# Sheet2.net
KiCad netlist of a schematic drawn in Altium Designer
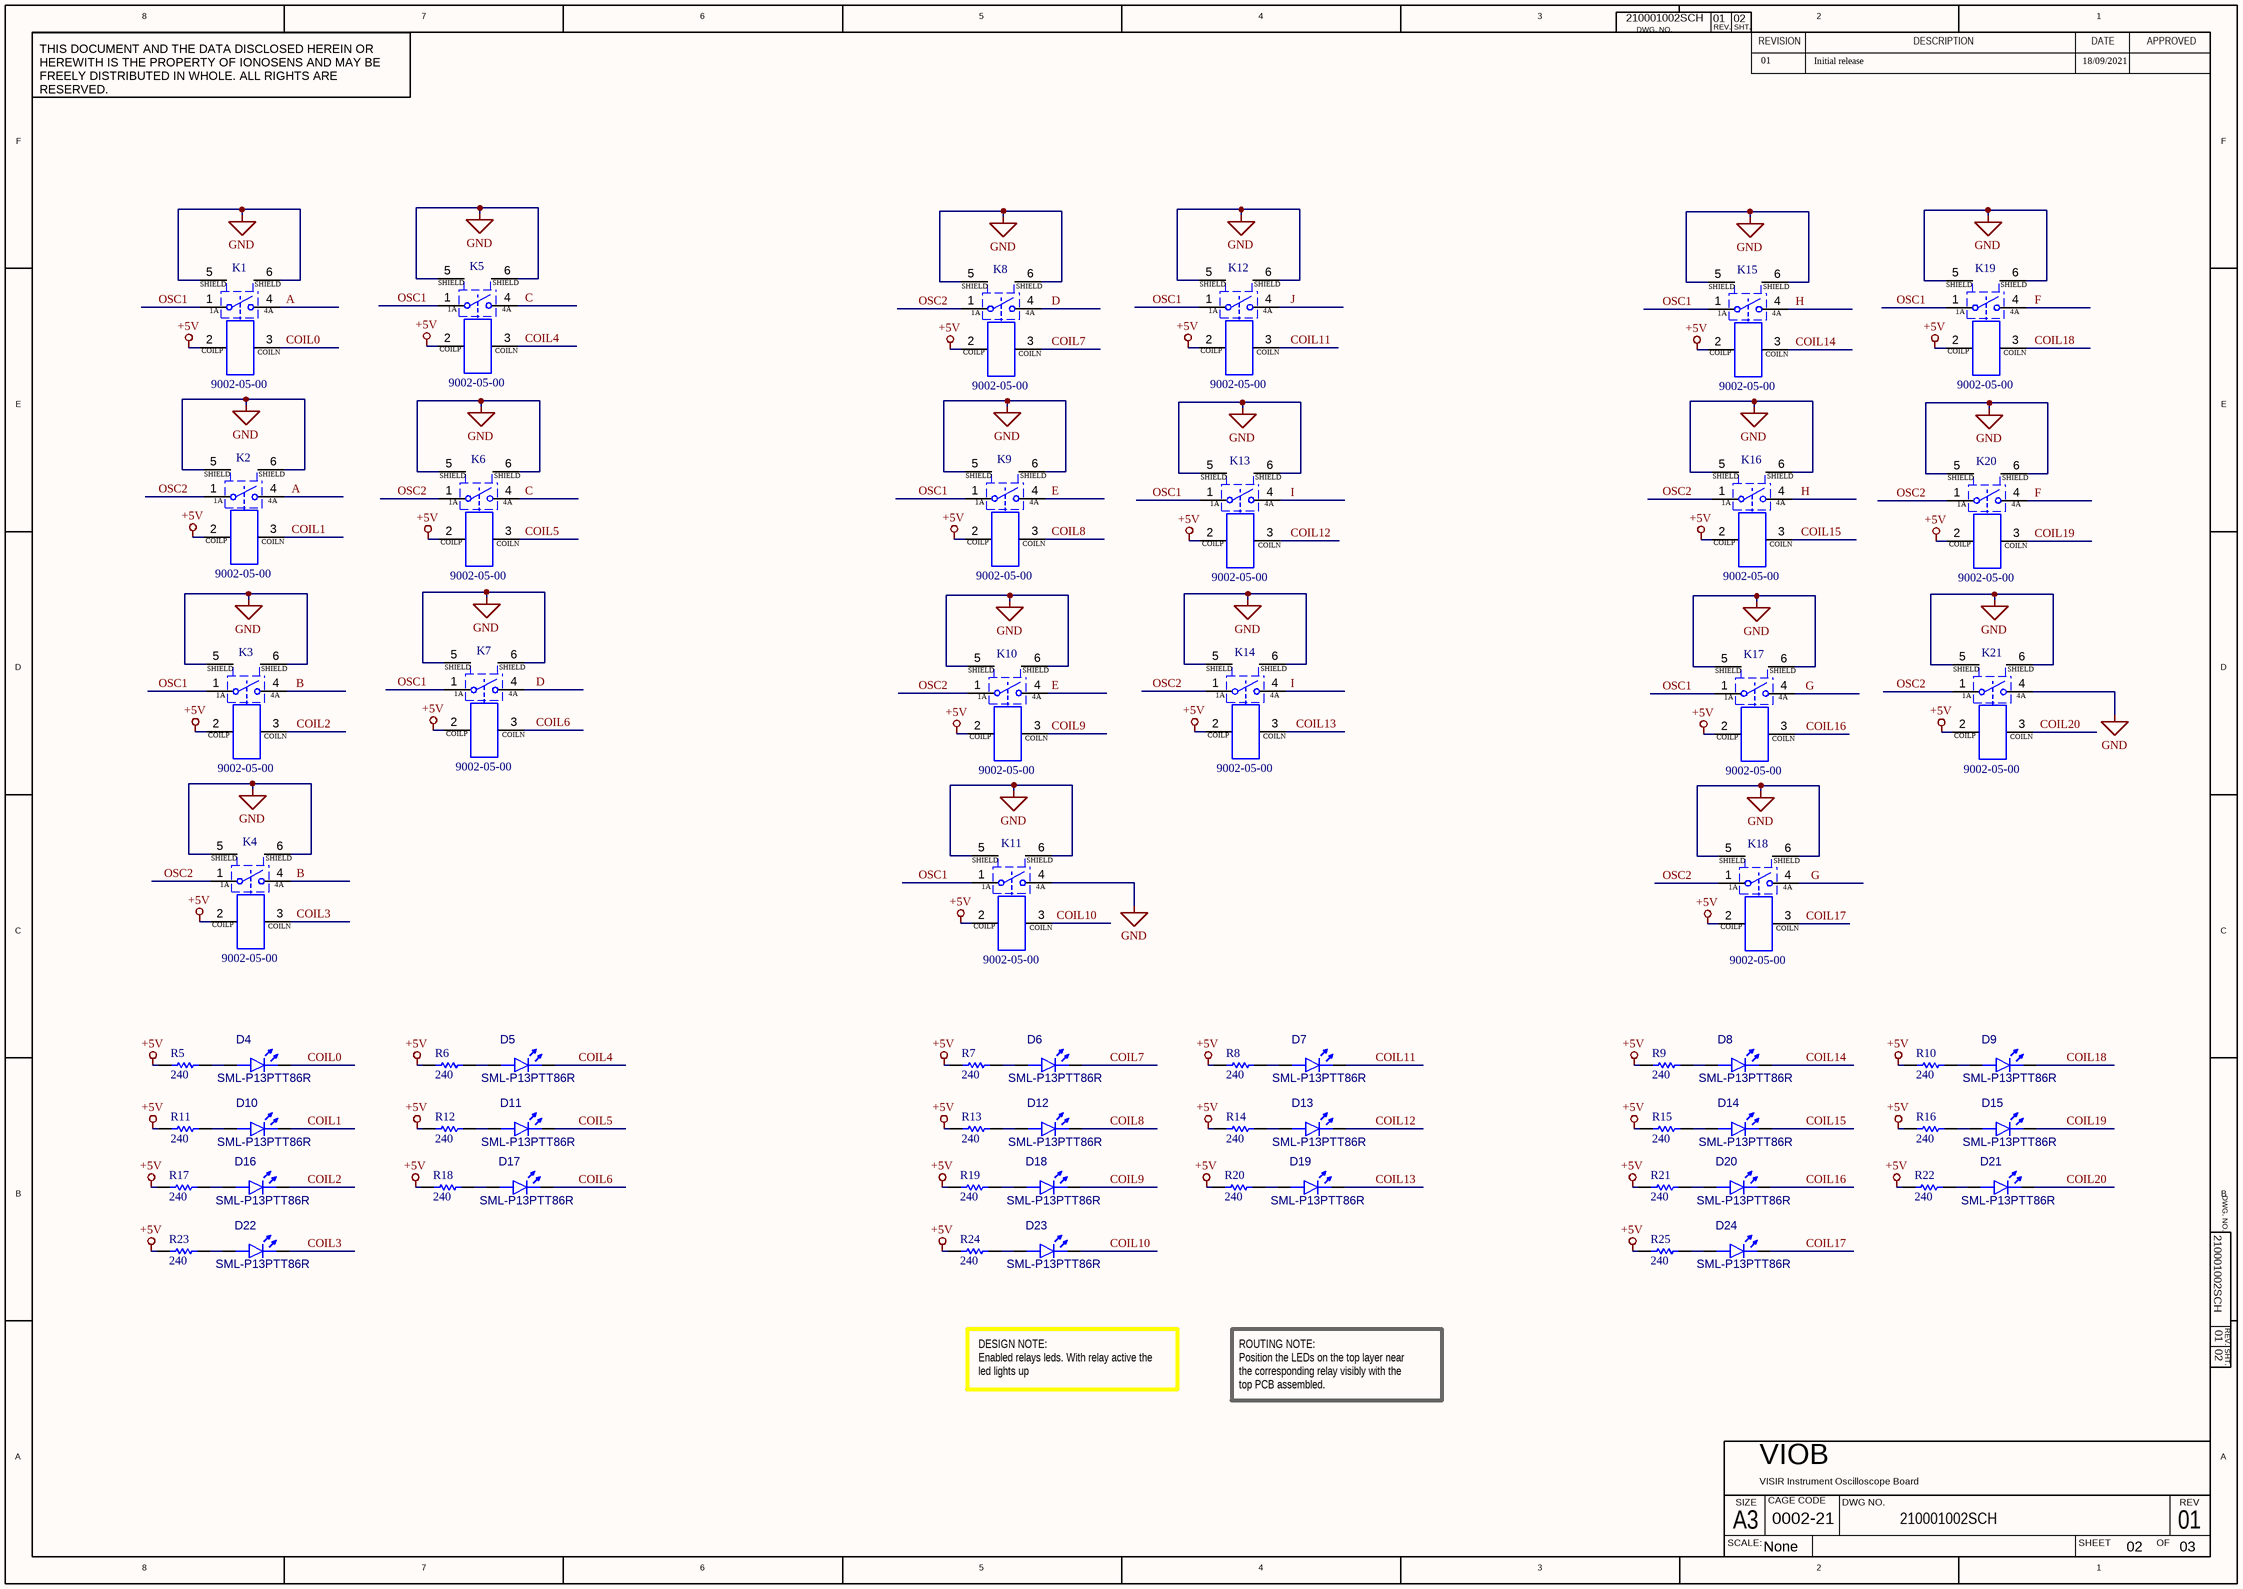
[diagram p0: Sheet2.SchDoc]

(export (version "E")
  (design (tool "Eeschema 10.0.6"))
  (components
    (comp (ref "D4")
      (value "SML-P13PTT86R")
      (footprint "DIOC1005X02R")
      (description "Led green 0402")
      (fields (field (name "MANUFACTURER") "ROHM"))
      (libsource (lib "<Company> Server") (part "LED"))
    )
    (comp (ref "D5")
      (value "SML-P13PTT86R")
      (footprint "DIOC1005X02R")
      (description "Led green 0402")
      (fields (field (name "MANUFACTURER") "ROHM"))
      (libsource (lib "<Company> Server") (part "LED"))
    )
    (comp (ref "D6")
      (value "SML-P13PTT86R")
      (footprint "DIOC1005X02R")
      (description "Led green 0402")
      (fields (field (name "MANUFACTURER") "ROHM"))
      (libsource (lib "<Company> Server") (part "LED"))
    )
    (comp (ref "D7")
      (value "SML-P13PTT86R")
      (footprint "DIOC1005X02R")
      (description "Led green 0402")
      (fields (field (name "MANUFACTURER") "ROHM"))
      (libsource (lib "<Company> Server") (part "LED"))
    )
    (comp (ref "D8")
      (value "SML-P13PTT86R")
      (footprint "DIOC1005X02R")
      (description "Led green 0402")
      (fields (field (name "MANUFACTURER") "ROHM"))
      (libsource (lib "<Company> Server") (part "LED"))
    )
    (comp (ref "D9")
      (value "SML-P13PTT86R")
      (footprint "DIOC1005X02R")
      (description "Led green 0402")
      (fields (field (name "MANUFACTURER") "ROHM"))
      (libsource (lib "<Company> Server") (part "LED"))
    )
    (comp (ref "D10")
      (value "SML-P13PTT86R")
      (footprint "DIOC1005X02R")
      (description "Led green 0402")
      (fields (field (name "MANUFACTURER") "ROHM"))
      (libsource (lib "<Company> Server") (part "LED"))
    )
    (comp (ref "D11")
      (value "SML-P13PTT86R")
      (footprint "DIOC1005X02R")
      (description "Led green 0402")
      (fields (field (name "MANUFACTURER") "ROHM"))
      (libsource (lib "<Company> Server") (part "LED"))
    )
    (comp (ref "D12")
      (value "SML-P13PTT86R")
      (footprint "DIOC1005X02R")
      (description "Led green 0402")
      (fields (field (name "MANUFACTURER") "ROHM"))
      (libsource (lib "<Company> Server") (part "LED"))
    )
    (comp (ref "D13")
      (value "SML-P13PTT86R")
      (footprint "DIOC1005X02R")
      (description "Led green 0402")
      (fields (field (name "MANUFACTURER") "ROHM"))
      (libsource (lib "<Company> Server") (part "LED"))
    )
    (comp (ref "D14")
      (value "SML-P13PTT86R")
      (footprint "DIOC1005X02R")
      (description "Led green 0402")
      (fields (field (name "MANUFACTURER") "ROHM"))
      (libsource (lib "<Company> Server") (part "LED"))
    )
    (comp (ref "D15")
      (value "SML-P13PTT86R")
      (footprint "DIOC1005X02R")
      (description "Led green 0402")
      (fields (field (name "MANUFACTURER") "ROHM"))
      (libsource (lib "<Company> Server") (part "LED"))
    )
    (comp (ref "D16")
      (value "SML-P13PTT86R")
      (footprint "DIOC1005X02R")
      (description "Led green 0402")
      (fields (field (name "MANUFACTURER") "ROHM"))
      (libsource (lib "<Company> Server") (part "LED"))
    )
    (comp (ref "D17")
      (value "SML-P13PTT86R")
      (footprint "DIOC1005X02R")
      (description "Led green 0402")
      (fields (field (name "MANUFACTURER") "ROHM"))
      (libsource (lib "<Company> Server") (part "LED"))
    )
    (comp (ref "D18")
      (value "SML-P13PTT86R")
      (footprint "DIOC1005X02R")
      (description "Led green 0402")
      (fields (field (name "MANUFACTURER") "ROHM"))
      (libsource (lib "<Company> Server") (part "LED"))
    )
    (comp (ref "D19")
      (value "SML-P13PTT86R")
      (footprint "DIOC1005X02R")
      (description "Led green 0402")
      (fields (field (name "MANUFACTURER") "ROHM"))
      (libsource (lib "<Company> Server") (part "LED"))
    )
    (comp (ref "D20")
      (value "SML-P13PTT86R")
      (footprint "DIOC1005X02R")
      (description "Led green 0402")
      (fields (field (name "MANUFACTURER") "ROHM"))
      (libsource (lib "<Company> Server") (part "LED"))
    )
    (comp (ref "D21")
      (value "SML-P13PTT86R")
      (footprint "DIOC1005X02R")
      (description "Led green 0402")
      (fields (field (name "MANUFACTURER") "ROHM"))
      (libsource (lib "<Company> Server") (part "LED"))
    )
    (comp (ref "D22")
      (value "SML-P13PTT86R")
      (footprint "DIOC1005X02R")
      (description "Led green 0402")
      (fields (field (name "MANUFACTURER") "ROHM"))
      (libsource (lib "<Company> Server") (part "LED"))
    )
    (comp (ref "D23")
      (value "SML-P13PTT86R")
      (footprint "DIOC1005X02R")
      (description "Led green 0402")
      (fields (field (name "MANUFACTURER") "ROHM"))
      (libsource (lib "<Company> Server") (part "LED"))
    )
    (comp (ref "D24")
      (value "SML-P13PTT86R")
      (footprint "DIOC1005X02R")
      (description "Led green 0402")
      (fields (field (name "MANUFACTURER") "ROHM"))
      (libsource (lib "<Company> Server") (part "LED"))
    )
    (comp (ref "K1")
      (value "9002-05-00")
      (footprint "SIP564W40P254L1980H810Q6 - Cloned")
      (description "Reed Relay 5VDC 350Ohm 0.5A SPST-NO THT")
      (fields (field (name "MANUFACTURER") "COTO"))
      (libsource (lib "<Company> Server") (part "9002-XX-XX"))
    )
    (comp (ref "K2")
      (value "9002-05-00")
      (footprint "SIP564W40P254L1980H810Q6 - Cloned")
      (description "Reed Relay 5VDC 350Ohm 0.5A SPST-NO THT")
      (fields (field (name "MANUFACTURER") "COTO"))
      (libsource (lib "<Company> Server") (part "9002-XX-XX"))
    )
    (comp (ref "K3")
      (value "9002-05-00")
      (footprint "SIP564W40P254L1980H810Q6 - Cloned")
      (description "Reed Relay 5VDC 350Ohm 0.5A SPST-NO THT")
      (fields (field (name "MANUFACTURER") "COTO"))
      (libsource (lib "<Company> Server") (part "9002-XX-XX"))
    )
    (comp (ref "K4")
      (value "9002-05-00")
      (footprint "SIP564W40P254L1980H810Q6 - Cloned")
      (description "Reed Relay 5VDC 350Ohm 0.5A SPST-NO THT")
      (fields (field (name "MANUFACTURER") "COTO"))
      (libsource (lib "<Company> Server") (part "9002-XX-XX"))
    )
    (comp (ref "K5")
      (value "9002-05-00")
      (footprint "SIP564W40P254L1980H810Q6 - Cloned")
      (description "Reed Relay 5VDC 350Ohm 0.5A SPST-NO THT")
      (fields (field (name "MANUFACTURER") "COTO"))
      (libsource (lib "<Company> Server") (part "9002-XX-XX"))
    )
    (comp (ref "K6")
      (value "9002-05-00")
      (footprint "SIP564W40P254L1980H810Q6 - Cloned")
      (description "Reed Relay 5VDC 350Ohm 0.5A SPST-NO THT")
      (fields (field (name "MANUFACTURER") "COTO"))
      (libsource (lib "<Company> Server") (part "9002-XX-XX"))
    )
    (comp (ref "K7")
      (value "9002-05-00")
      (footprint "SIP564W40P254L1980H810Q6 - Cloned")
      (description "Reed Relay 5VDC 350Ohm 0.5A SPST-NO THT")
      (fields (field (name "MANUFACTURER") "COTO"))
      (libsource (lib "<Company> Server") (part "9002-XX-XX"))
    )
    (comp (ref "K8")
      (value "9002-05-00")
      (footprint "SIP564W40P254L1980H810Q6 - Cloned")
      (description "Reed Relay 5VDC 350Ohm 0.5A SPST-NO THT")
      (fields (field (name "MANUFACTURER") "COTO"))
      (libsource (lib "<Company> Server") (part "9002-XX-XX"))
    )
    (comp (ref "K9")
      (value "9002-05-00")
      (footprint "SIP564W40P254L1980H810Q6 - Cloned")
      (description "Reed Relay 5VDC 350Ohm 0.5A SPST-NO THT")
      (fields (field (name "MANUFACTURER") "COTO"))
      (libsource (lib "<Company> Server") (part "9002-XX-XX"))
    )
    (comp (ref "K10")
      (value "9002-05-00")
      (footprint "SIP564W40P254L1980H810Q6 - Cloned")
      (description "Reed Relay 5VDC 350Ohm 0.5A SPST-NO THT")
      (fields (field (name "MANUFACTURER") "COTO"))
      (libsource (lib "<Company> Server") (part "9002-XX-XX"))
    )
    (comp (ref "K11")
      (value "9002-05-00")
      (footprint "SIP564W40P254L1980H810Q6 - Cloned")
      (description "Reed Relay 5VDC 350Ohm 0.5A SPST-NO THT")
      (fields (field (name "MANUFACTURER") "COTO"))
      (libsource (lib "<Company> Server") (part "9002-XX-XX"))
    )
    (comp (ref "K12")
      (value "9002-05-00")
      (footprint "SIP564W40P254L1980H810Q6 - Cloned")
      (description "Reed Relay 5VDC 350Ohm 0.5A SPST-NO THT")
      (fields (field (name "MANUFACTURER") "COTO"))
      (libsource (lib "<Company> Server") (part "9002-XX-XX"))
    )
    (comp (ref "K13")
      (value "9002-05-00")
      (footprint "SIP564W40P254L1980H810Q6 - Cloned")
      (description "Reed Relay 5VDC 350Ohm 0.5A SPST-NO THT")
      (fields (field (name "MANUFACTURER") "COTO"))
      (libsource (lib "<Company> Server") (part "9002-XX-XX"))
    )
    (comp (ref "K14")
      (value "9002-05-00")
      (footprint "SIP564W40P254L1980H810Q6 - Cloned")
      (description "Reed Relay 5VDC 350Ohm 0.5A SPST-NO THT")
      (fields (field (name "MANUFACTURER") "COTO"))
      (libsource (lib "<Company> Server") (part "9002-XX-XX"))
    )
    (comp (ref "K15")
      (value "9002-05-00")
      (footprint "SIP564W40P254L1980H810Q6 - Cloned")
      (description "Reed Relay 5VDC 350Ohm 0.5A SPST-NO THT")
      (fields (field (name "MANUFACTURER") "COTO"))
      (libsource (lib "<Company> Server") (part "9002-XX-XX"))
    )
    (comp (ref "K16")
      (value "9002-05-00")
      (footprint "SIP564W40P254L1980H810Q6 - Cloned")
      (description "Reed Relay 5VDC 350Ohm 0.5A SPST-NO THT")
      (fields (field (name "MANUFACTURER") "COTO"))
      (libsource (lib "<Company> Server") (part "9002-XX-XX"))
    )
    (comp (ref "K17")
      (value "9002-05-00")
      (footprint "SIP564W40P254L1980H810Q6 - Cloned")
      (description "Reed Relay 5VDC 350Ohm 0.5A SPST-NO THT")
      (fields (field (name "MANUFACTURER") "COTO"))
      (libsource (lib "<Company> Server") (part "9002-XX-XX"))
    )
    (comp (ref "K18")
      (value "9002-05-00")
      (footprint "SIP564W40P254L1980H810Q6 - Cloned")
      (description "Reed Relay 5VDC 350Ohm 0.5A SPST-NO THT")
      (fields (field (name "MANUFACTURER") "COTO"))
      (libsource (lib "<Company> Server") (part "9002-XX-XX"))
    )
    (comp (ref "K19")
      (value "9002-05-00")
      (footprint "SIP564W40P254L1980H810Q6 - Cloned")
      (description "Reed Relay 5VDC 350Ohm 0.5A SPST-NO THT")
      (fields (field (name "MANUFACTURER") "COTO"))
      (libsource (lib "<Company> Server") (part "9002-XX-XX"))
    )
    (comp (ref "K20")
      (value "9002-05-00")
      (footprint "SIP564W40P254L1980H810Q6 - Cloned")
      (description "Reed Relay 5VDC 350Ohm 0.5A SPST-NO THT")
      (fields (field (name "MANUFACTURER") "COTO"))
      (libsource (lib "<Company> Server") (part "9002-XX-XX"))
    )
    (comp (ref "K21")
      (value "9002-05-00")
      (footprint "SIP564W40P254L1980H810Q6 - Cloned")
      (description "Reed Relay 5VDC 350Ohm 0.5A SPST-NO THT")
      (fields (field (name "MANUFACTURER") "COTO"))
      (libsource (lib "<Company> Server") (part "9002-XX-XX"))
    )
    (comp (ref "R5")
      (value "240")
      (footprint "RESC1005X04M")
      (description "RES SMD 240 OHM 1% 1/16W 0402")
      (fields (field (name "MANUFACTURER") "Yageo") (field (name "TOLERANCE") "1%"))
      (libsource (lib "<Company> Server") (part "Resistor"))
    )
    (comp (ref "R6")
      (value "240")
      (footprint "RESC1005X04M")
      (description "RES SMD 240 OHM 1% 1/16W 0402")
      (fields (field (name "MANUFACTURER") "Yageo") (field (name "TOLERANCE") "1%"))
      (libsource (lib "<Company> Server") (part "Resistor"))
    )
    (comp (ref "R7")
      (value "240")
      (footprint "RESC1005X04M")
      (description "RES SMD 240 OHM 1% 1/16W 0402")
      (fields (field (name "MANUFACTURER") "Yageo") (field (name "TOLERANCE") "1%"))
      (libsource (lib "<Company> Server") (part "Resistor"))
    )
    (comp (ref "R8")
      (value "240")
      (footprint "RESC1005X04M")
      (description "RES SMD 240 OHM 1% 1/16W 0402")
      (fields (field (name "MANUFACTURER") "Yageo") (field (name "TOLERANCE") "1%"))
      (libsource (lib "<Company> Server") (part "Resistor"))
    )
    (comp (ref "R9")
      (value "240")
      (footprint "RESC1005X04M")
      (description "RES SMD 240 OHM 1% 1/16W 0402")
      (fields (field (name "MANUFACTURER") "Yageo") (field (name "TOLERANCE") "1%"))
      (libsource (lib "<Company> Server") (part "Resistor"))
    )
    (comp (ref "R10")
      (value "240")
      (footprint "RESC1005X04M")
      (description "RES SMD 240 OHM 1% 1/16W 0402")
      (fields (field (name "MANUFACTURER") "Yageo") (field (name "TOLERANCE") "1%"))
      (libsource (lib "<Company> Server") (part "Resistor"))
    )
    (comp (ref "R11")
      (value "240")
      (footprint "RESC1005X04M")
      (description "RES SMD 240 OHM 1% 1/16W 0402")
      (fields (field (name "MANUFACTURER") "Yageo") (field (name "TOLERANCE") "1%"))
      (libsource (lib "<Company> Server") (part "Resistor"))
    )
    (comp (ref "R12")
      (value "240")
      (footprint "RESC1005X04M")
      (description "RES SMD 240 OHM 1% 1/16W 0402")
      (fields (field (name "MANUFACTURER") "Yageo") (field (name "TOLERANCE") "1%"))
      (libsource (lib "<Company> Server") (part "Resistor"))
    )
    (comp (ref "R13")
      (value "240")
      (footprint "RESC1005X04M")
      (description "RES SMD 240 OHM 1% 1/16W 0402")
      (fields (field (name "MANUFACTURER") "Yageo") (field (name "TOLERANCE") "1%"))
      (libsource (lib "<Company> Server") (part "Resistor"))
    )
    (comp (ref "R14")
      (value "240")
      (footprint "RESC1005X04M")
      (description "RES SMD 240 OHM 1% 1/16W 0402")
      (fields (field (name "MANUFACTURER") "Yageo") (field (name "TOLERANCE") "1%"))
      (libsource (lib "<Company> Server") (part "Resistor"))
    )
    (comp (ref "R15")
      (value "240")
      (footprint "RESC1005X04M")
      (description "RES SMD 240 OHM 1% 1/16W 0402")
      (fields (field (name "MANUFACTURER") "Yageo") (field (name "TOLERANCE") "1%"))
      (libsource (lib "<Company> Server") (part "Resistor"))
    )
    (comp (ref "R16")
      (value "240")
      (footprint "RESC1005X04M")
      (description "RES SMD 240 OHM 1% 1/16W 0402")
      (fields (field (name "MANUFACTURER") "Yageo") (field (name "TOLERANCE") "1%"))
      (libsource (lib "<Company> Server") (part "Resistor"))
    )
    (comp (ref "R17")
      (value "240")
      (footprint "RESC1005X04M")
      (description "RES SMD 240 OHM 1% 1/16W 0402")
      (fields (field (name "MANUFACTURER") "Yageo") (field (name "TOLERANCE") "1%"))
      (libsource (lib "<Company> Server") (part "Resistor"))
    )
    (comp (ref "R18")
      (value "240")
      (footprint "RESC1005X04M")
      (description "RES SMD 240 OHM 1% 1/16W 0402")
      (fields (field (name "MANUFACTURER") "Yageo") (field (name "TOLERANCE") "1%"))
      (libsource (lib "<Company> Server") (part "Resistor"))
    )
    (comp (ref "R19")
      (value "240")
      (footprint "RESC1005X04M")
      (description "RES SMD 240 OHM 1% 1/16W 0402")
      (fields (field (name "MANUFACTURER") "Yageo") (field (name "TOLERANCE") "1%"))
      (libsource (lib "<Company> Server") (part "Resistor"))
    )
    (comp (ref "R20")
      (value "240")
      (footprint "RESC1005X04M")
      (description "RES SMD 240 OHM 1% 1/16W 0402")
      (fields (field (name "MANUFACTURER") "Yageo") (field (name "TOLERANCE") "1%"))
      (libsource (lib "<Company> Server") (part "Resistor"))
    )
    (comp (ref "R21")
      (value "240")
      (footprint "RESC1005X04M")
      (description "RES SMD 240 OHM 1% 1/16W 0402")
      (fields (field (name "MANUFACTURER") "Yageo") (field (name "TOLERANCE") "1%"))
      (libsource (lib "<Company> Server") (part "Resistor"))
    )
    (comp (ref "R22")
      (value "240")
      (footprint "RESC1005X04M")
      (description "RES SMD 240 OHM 1% 1/16W 0402")
      (fields (field (name "MANUFACTURER") "Yageo") (field (name "TOLERANCE") "1%"))
      (libsource (lib "<Company> Server") (part "Resistor"))
    )
    (comp (ref "R23")
      (value "240")
      (footprint "RESC1005X04M")
      (description "RES SMD 240 OHM 1% 1/16W 0402")
      (fields (field (name "MANUFACTURER") "Yageo") (field (name "TOLERANCE") "1%"))
      (libsource (lib "<Company> Server") (part "Resistor"))
    )
    (comp (ref "R24")
      (value "240")
      (footprint "RESC1005X04M")
      (description "RES SMD 240 OHM 1% 1/16W 0402")
      (fields (field (name "MANUFACTURER") "Yageo") (field (name "TOLERANCE") "1%"))
      (libsource (lib "<Company> Server") (part "Resistor"))
    )
    (comp (ref "R25")
      (value "240")
      (footprint "RESC1005X04M")
      (description "RES SMD 240 OHM 1% 1/16W 0402")
      (fields (field (name "MANUFACTURER") "Yageo") (field (name "TOLERANCE") "1%"))
      (libsource (lib "<Company> Server") (part "Resistor"))
    )
  )
  (nets
    (net (code "1") (name "+5V") (class "Default")
      (node (ref "K1") (pin "2") (pinfunction "COILP_2") (pintype "passive"))
      (node (ref "K10") (pin "2") (pinfunction "COILP_2") (pintype "passive"))
      (node (ref "K11") (pin "2") (pinfunction "COILP_2") (pintype "passive"))
      (node (ref "K12") (pin "2") (pinfunction "COILP_2") (pintype "passive"))
      (node (ref "K13") (pin "2") (pinfunction "COILP_2") (pintype "passive"))
      (node (ref "K14") (pin "2") (pinfunction "COILP_2") (pintype "passive"))
      (node (ref "K15") (pin "2") (pinfunction "COILP_2") (pintype "passive"))
      (node (ref "K16") (pin "2") (pinfunction "COILP_2") (pintype "passive"))
      (node (ref "K17") (pin "2") (pinfunction "COILP_2") (pintype "passive"))
      (node (ref "K18") (pin "2") (pinfunction "COILP_2") (pintype "passive"))
      (node (ref "K19") (pin "2") (pinfunction "COILP_2") (pintype "passive"))
      (node (ref "K2") (pin "2") (pinfunction "COILP_2") (pintype "passive"))
      (node (ref "K20") (pin "2") (pinfunction "COILP_2") (pintype "passive"))
      (node (ref "K21") (pin "2") (pinfunction "COILP_2") (pintype "passive"))
      (node (ref "K3") (pin "2") (pinfunction "COILP_2") (pintype "passive"))
      (node (ref "K4") (pin "2") (pinfunction "COILP_2") (pintype "passive"))
      (node (ref "K5") (pin "2") (pinfunction "COILP_2") (pintype "passive"))
      (node (ref "K6") (pin "2") (pinfunction "COILP_2") (pintype "passive"))
      (node (ref "K7") (pin "2") (pinfunction "COILP_2") (pintype "passive"))
      (node (ref "K8") (pin "2") (pinfunction "COILP_2") (pintype "passive"))
      (node (ref "K9") (pin "2") (pinfunction "COILP_2") (pintype "passive"))
      (node (ref "R10") (pin "1") (pinfunction "1_1") (pintype "passive"))
      (node (ref "R11") (pin "1") (pinfunction "1_1") (pintype "passive"))
      (node (ref "R12") (pin "1") (pinfunction "1_1") (pintype "passive"))
      (node (ref "R13") (pin "1") (pinfunction "1_1") (pintype "passive"))
      (node (ref "R14") (pin "1") (pinfunction "1_1") (pintype "passive"))
      (node (ref "R15") (pin "1") (pinfunction "1_1") (pintype "passive"))
      (node (ref "R16") (pin "1") (pinfunction "1_1") (pintype "passive"))
      (node (ref "R17") (pin "1") (pinfunction "1_1") (pintype "passive"))
      (node (ref "R18") (pin "1") (pinfunction "1_1") (pintype "passive"))
      (node (ref "R19") (pin "1") (pinfunction "1_1") (pintype "passive"))
      (node (ref "R20") (pin "1") (pinfunction "1_1") (pintype "passive"))
      (node (ref "R21") (pin "1") (pinfunction "1_1") (pintype "passive"))
      (node (ref "R22") (pin "1") (pinfunction "1_1") (pintype "passive"))
      (node (ref "R23") (pin "1") (pinfunction "1_1") (pintype "passive"))
      (node (ref "R24") (pin "1") (pinfunction "1_1") (pintype "passive"))
      (node (ref "R25") (pin "1") (pinfunction "1_1") (pintype "passive"))
      (node (ref "R5") (pin "1") (pinfunction "1_1") (pintype "passive"))
      (node (ref "R6") (pin "1") (pinfunction "1_1") (pintype "passive"))
      (node (ref "R7") (pin "1") (pinfunction "1_1") (pintype "passive"))
      (node (ref "R8") (pin "1") (pinfunction "1_1") (pintype "passive"))
      (node (ref "R9") (pin "1") (pinfunction "1_1") (pintype "passive"))
    )
    (net (code "2") (name "/A") (class "Default")
      (node (ref "K1") (pin "4") (pinfunction "4A_4") (pintype "passive"))
      (node (ref "K2") (pin "4") (pinfunction "4A_4") (pintype "passive"))
    )
    (net (code "3") (name "/B") (class "Default")
      (node (ref "K3") (pin "4") (pinfunction "4A_4") (pintype "passive"))
      (node (ref "K4") (pin "4") (pinfunction "4A_4") (pintype "passive"))
    )
    (net (code "4") (name "/C") (class "Default")
      (node (ref "K5") (pin "4") (pinfunction "4A_4") (pintype "passive"))
      (node (ref "K6") (pin "4") (pinfunction "4A_4") (pintype "passive"))
    )
    (net (code "5") (name "/COIL0") (class "Default")
      (node (ref "D4") (pin "1") (pinfunction "K_1") (pintype "passive"))
      (node (ref "K1") (pin "3") (pinfunction "COILN_3") (pintype "passive"))
    )
    (net (code "6") (name "/COIL1") (class "Default")
      (node (ref "D10") (pin "1") (pinfunction "K_1") (pintype "passive"))
      (node (ref "K2") (pin "3") (pinfunction "COILN_3") (pintype "passive"))
    )
    (net (code "7") (name "/COIL2") (class "Default")
      (node (ref "D16") (pin "1") (pinfunction "K_1") (pintype "passive"))
      (node (ref "K3") (pin "3") (pinfunction "COILN_3") (pintype "passive"))
    )
    (net (code "8") (name "/COIL3") (class "Default")
      (node (ref "D22") (pin "1") (pinfunction "K_1") (pintype "passive"))
      (node (ref "K4") (pin "3") (pinfunction "COILN_3") (pintype "passive"))
    )
    (net (code "9") (name "/COIL4") (class "Default")
      (node (ref "D5") (pin "1") (pinfunction "K_1") (pintype "passive"))
      (node (ref "K5") (pin "3") (pinfunction "COILN_3") (pintype "passive"))
    )
    (net (code "10") (name "/COIL5") (class "Default")
      (node (ref "D11") (pin "1") (pinfunction "K_1") (pintype "passive"))
      (node (ref "K6") (pin "3") (pinfunction "COILN_3") (pintype "passive"))
    )
    (net (code "11") (name "/COIL6") (class "Default")
      (node (ref "D17") (pin "1") (pinfunction "K_1") (pintype "passive"))
      (node (ref "K7") (pin "3") (pinfunction "COILN_3") (pintype "passive"))
    )
    (net (code "12") (name "/COIL7") (class "Default")
      (node (ref "D6") (pin "1") (pinfunction "K_1") (pintype "passive"))
      (node (ref "K8") (pin "3") (pinfunction "COILN_3") (pintype "passive"))
    )
    (net (code "13") (name "/COIL8") (class "Default")
      (node (ref "D12") (pin "1") (pinfunction "K_1") (pintype "passive"))
      (node (ref "K9") (pin "3") (pinfunction "COILN_3") (pintype "passive"))
    )
    (net (code "14") (name "/COIL9") (class "Default")
      (node (ref "D18") (pin "1") (pinfunction "K_1") (pintype "passive"))
      (node (ref "K10") (pin "3") (pinfunction "COILN_3") (pintype "passive"))
    )
    (net (code "15") (name "/COIL10") (class "Default")
      (node (ref "D23") (pin "1") (pinfunction "K_1") (pintype "passive"))
      (node (ref "K11") (pin "3") (pinfunction "COILN_3") (pintype "passive"))
    )
    (net (code "16") (name "/COIL11") (class "Default")
      (node (ref "D7") (pin "1") (pinfunction "K_1") (pintype "passive"))
      (node (ref "K12") (pin "3") (pinfunction "COILN_3") (pintype "passive"))
    )
    (net (code "17") (name "/COIL12") (class "Default")
      (node (ref "D13") (pin "1") (pinfunction "K_1") (pintype "passive"))
      (node (ref "K13") (pin "3") (pinfunction "COILN_3") (pintype "passive"))
    )
    (net (code "18") (name "/COIL13") (class "Default")
      (node (ref "D19") (pin "1") (pinfunction "K_1") (pintype "passive"))
      (node (ref "K14") (pin "3") (pinfunction "COILN_3") (pintype "passive"))
    )
    (net (code "19") (name "/COIL14") (class "Default")
      (node (ref "D8") (pin "1") (pinfunction "K_1") (pintype "passive"))
      (node (ref "K15") (pin "3") (pinfunction "COILN_3") (pintype "passive"))
    )
    (net (code "20") (name "/COIL15") (class "Default")
      (node (ref "D14") (pin "1") (pinfunction "K_1") (pintype "passive"))
      (node (ref "K16") (pin "3") (pinfunction "COILN_3") (pintype "passive"))
    )
    (net (code "21") (name "/COIL16") (class "Default")
      (node (ref "D20") (pin "1") (pinfunction "K_1") (pintype "passive"))
      (node (ref "K17") (pin "3") (pinfunction "COILN_3") (pintype "passive"))
    )
    (net (code "22") (name "/COIL17") (class "Default")
      (node (ref "D24") (pin "1") (pinfunction "K_1") (pintype "passive"))
      (node (ref "K18") (pin "3") (pinfunction "COILN_3") (pintype "passive"))
    )
    (net (code "23") (name "/COIL18") (class "Default")
      (node (ref "D9") (pin "1") (pinfunction "K_1") (pintype "passive"))
      (node (ref "K19") (pin "3") (pinfunction "COILN_3") (pintype "passive"))
    )
    (net (code "24") (name "/COIL19") (class "Default")
      (node (ref "D15") (pin "1") (pinfunction "K_1") (pintype "passive"))
      (node (ref "K20") (pin "3") (pinfunction "COILN_3") (pintype "passive"))
    )
    (net (code "25") (name "/COIL20") (class "Default")
      (node (ref "D21") (pin "1") (pinfunction "K_1") (pintype "passive"))
      (node (ref "K21") (pin "3") (pinfunction "COILN_3") (pintype "passive"))
    )
    (net (code "26") (name "/D") (class "Default")
      (node (ref "K7") (pin "4") (pinfunction "4A_4") (pintype "passive"))
      (node (ref "K8") (pin "4") (pinfunction "4A_4") (pintype "passive"))
    )
    (net (code "27") (name "/E") (class "Default")
      (node (ref "K10") (pin "4") (pinfunction "4A_4") (pintype "passive"))
      (node (ref "K9") (pin "4") (pinfunction "4A_4") (pintype "passive"))
    )
    (net (code "28") (name "/F") (class "Default")
      (node (ref "K19") (pin "4") (pinfunction "4A_4") (pintype "passive"))
      (node (ref "K20") (pin "4") (pinfunction "4A_4") (pintype "passive"))
    )
    (net (code "29") (name "/G") (class "Default")
      (node (ref "K17") (pin "4") (pinfunction "4A_4") (pintype "passive"))
      (node (ref "K18") (pin "4") (pinfunction "4A_4") (pintype "passive"))
    )
    (net (code "30") (name "/H") (class "Default")
      (node (ref "K15") (pin "4") (pinfunction "4A_4") (pintype "passive"))
      (node (ref "K16") (pin "4") (pinfunction "4A_4") (pintype "passive"))
    )
    (net (code "31") (name "/I") (class "Default")
      (node (ref "K13") (pin "4") (pinfunction "4A_4") (pintype "passive"))
      (node (ref "K14") (pin "4") (pinfunction "4A_4") (pintype "passive"))
    )
    (net (code "32") (name "/J") (class "Default")
      (node (ref "K12") (pin "4") (pinfunction "4A_4") (pintype "passive"))
    )
    (net (code "33") (name "/OSC1") (class "Default")
      (node (ref "K1") (pin "1") (pinfunction "1A_1") (pintype "passive"))
      (node (ref "K11") (pin "1") (pinfunction "1A_1") (pintype "passive"))
      (node (ref "K12") (pin "1") (pinfunction "1A_1") (pintype "passive"))
      (node (ref "K13") (pin "1") (pinfunction "1A_1") (pintype "passive"))
      (node (ref "K15") (pin "1") (pinfunction "1A_1") (pintype "passive"))
      (node (ref "K17") (pin "1") (pinfunction "1A_1") (pintype "passive"))
      (node (ref "K19") (pin "1") (pinfunction "1A_1") (pintype "passive"))
      (node (ref "K3") (pin "1") (pinfunction "1A_1") (pintype "passive"))
      (node (ref "K5") (pin "1") (pinfunction "1A_1") (pintype "passive"))
      (node (ref "K7") (pin "1") (pinfunction "1A_1") (pintype "passive"))
      (node (ref "K9") (pin "1") (pinfunction "1A_1") (pintype "passive"))
    )
    (net (code "34") (name "/OSC2") (class "Default")
      (node (ref "K10") (pin "1") (pinfunction "1A_1") (pintype "passive"))
      (node (ref "K14") (pin "1") (pinfunction "1A_1") (pintype "passive"))
      (node (ref "K16") (pin "1") (pinfunction "1A_1") (pintype "passive"))
      (node (ref "K18") (pin "1") (pinfunction "1A_1") (pintype "passive"))
      (node (ref "K2") (pin "1") (pinfunction "1A_1") (pintype "passive"))
      (node (ref "K20") (pin "1") (pinfunction "1A_1") (pintype "passive"))
      (node (ref "K21") (pin "1") (pinfunction "1A_1") (pintype "passive"))
      (node (ref "K4") (pin "1") (pinfunction "1A_1") (pintype "passive"))
      (node (ref "K6") (pin "1") (pinfunction "1A_1") (pintype "passive"))
      (node (ref "K8") (pin "1") (pinfunction "1A_1") (pintype "passive"))
    )
    (net (code "35") (name "GND") (class "Default")
      (node (ref "K1") (pin "5") (pinfunction "Shield_5") (pintype "passive"))
      (node (ref "K1") (pin "6") (pinfunction "Shield_6") (pintype "passive"))
      (node (ref "K10") (pin "5") (pinfunction "Shield_5") (pintype "passive"))
      (node (ref "K10") (pin "6") (pinfunction "Shield_6") (pintype "passive"))
      (node (ref "K11") (pin "4") (pinfunction "4A_4") (pintype "passive"))
      (node (ref "K11") (pin "5") (pinfunction "Shield_5") (pintype "passive"))
      (node (ref "K11") (pin "6") (pinfunction "Shield_6") (pintype "passive"))
      (node (ref "K12") (pin "5") (pinfunction "Shield_5") (pintype "passive"))
      (node (ref "K12") (pin "6") (pinfunction "Shield_6") (pintype "passive"))
      (node (ref "K13") (pin "5") (pinfunction "Shield_5") (pintype "passive"))
      (node (ref "K13") (pin "6") (pinfunction "Shield_6") (pintype "passive"))
      (node (ref "K14") (pin "5") (pinfunction "Shield_5") (pintype "passive"))
      (node (ref "K14") (pin "6") (pinfunction "Shield_6") (pintype "passive"))
      (node (ref "K15") (pin "5") (pinfunction "Shield_5") (pintype "passive"))
      (node (ref "K15") (pin "6") (pinfunction "Shield_6") (pintype "passive"))
      (node (ref "K16") (pin "5") (pinfunction "Shield_5") (pintype "passive"))
      (node (ref "K16") (pin "6") (pinfunction "Shield_6") (pintype "passive"))
      (node (ref "K17") (pin "5") (pinfunction "Shield_5") (pintype "passive"))
      (node (ref "K17") (pin "6") (pinfunction "Shield_6") (pintype "passive"))
      (node (ref "K18") (pin "5") (pinfunction "Shield_5") (pintype "passive"))
      (node (ref "K18") (pin "6") (pinfunction "Shield_6") (pintype "passive"))
      (node (ref "K19") (pin "5") (pinfunction "Shield_5") (pintype "passive"))
      (node (ref "K19") (pin "6") (pinfunction "Shield_6") (pintype "passive"))
      (node (ref "K2") (pin "5") (pinfunction "Shield_5") (pintype "passive"))
      (node (ref "K2") (pin "6") (pinfunction "Shield_6") (pintype "passive"))
      (node (ref "K20") (pin "5") (pinfunction "Shield_5") (pintype "passive"))
      (node (ref "K20") (pin "6") (pinfunction "Shield_6") (pintype "passive"))
      (node (ref "K21") (pin "4") (pinfunction "4A_4") (pintype "passive"))
      (node (ref "K21") (pin "5") (pinfunction "Shield_5") (pintype "passive"))
      (node (ref "K21") (pin "6") (pinfunction "Shield_6") (pintype "passive"))
      (node (ref "K3") (pin "5") (pinfunction "Shield_5") (pintype "passive"))
      (node (ref "K3") (pin "6") (pinfunction "Shield_6") (pintype "passive"))
      (node (ref "K4") (pin "5") (pinfunction "Shield_5") (pintype "passive"))
      (node (ref "K4") (pin "6") (pinfunction "Shield_6") (pintype "passive"))
      (node (ref "K5") (pin "5") (pinfunction "Shield_5") (pintype "passive"))
      (node (ref "K5") (pin "6") (pinfunction "Shield_6") (pintype "passive"))
      (node (ref "K6") (pin "5") (pinfunction "Shield_5") (pintype "passive"))
      (node (ref "K6") (pin "6") (pinfunction "Shield_6") (pintype "passive"))
      (node (ref "K7") (pin "5") (pinfunction "Shield_5") (pintype "passive"))
      (node (ref "K7") (pin "6") (pinfunction "Shield_6") (pintype "passive"))
      (node (ref "K8") (pin "5") (pinfunction "Shield_5") (pintype "passive"))
      (node (ref "K8") (pin "6") (pinfunction "Shield_6") (pintype "passive"))
      (node (ref "K9") (pin "5") (pinfunction "Shield_5") (pintype "passive"))
      (node (ref "K9") (pin "6") (pinfunction "Shield_6") (pintype "passive"))
    )
    (net (code "36") (name "Net-(D4-A)") (class "Default")
      (node (ref "D4") (pin "2") (pinfunction "A_2") (pintype "passive"))
      (node (ref "R5") (pin "2") (pinfunction "2_2") (pintype "passive"))
    )
    (net (code "37") (name "Net-(D5-A)") (class "Default")
      (node (ref "D5") (pin "2") (pinfunction "A_2") (pintype "passive"))
      (node (ref "R6") (pin "2") (pinfunction "2_2") (pintype "passive"))
    )
    (net (code "38") (name "Net-(D6-A)") (class "Default")
      (node (ref "D6") (pin "2") (pinfunction "A_2") (pintype "passive"))
      (node (ref "R7") (pin "2") (pinfunction "2_2") (pintype "passive"))
    )
    (net (code "39") (name "Net-(D7-A)") (class "Default")
      (node (ref "D7") (pin "2") (pinfunction "A_2") (pintype "passive"))
      (node (ref "R8") (pin "2") (pinfunction "2_2") (pintype "passive"))
    )
    (net (code "40") (name "Net-(D8-A)") (class "Default")
      (node (ref "D8") (pin "2") (pinfunction "A_2") (pintype "passive"))
      (node (ref "R9") (pin "2") (pinfunction "2_2") (pintype "passive"))
    )
    (net (code "41") (name "Net-(D9-A)") (class "Default")
      (node (ref "D9") (pin "2") (pinfunction "A_2") (pintype "passive"))
      (node (ref "R10") (pin "2") (pinfunction "2_2") (pintype "passive"))
    )
    (net (code "42") (name "Net-(D10-A)") (class "Default")
      (node (ref "D10") (pin "2") (pinfunction "A_2") (pintype "passive"))
      (node (ref "R11") (pin "2") (pinfunction "2_2") (pintype "passive"))
    )
    (net (code "43") (name "Net-(D11-A)") (class "Default")
      (node (ref "D11") (pin "2") (pinfunction "A_2") (pintype "passive"))
      (node (ref "R12") (pin "2") (pinfunction "2_2") (pintype "passive"))
    )
    (net (code "44") (name "Net-(D12-A)") (class "Default")
      (node (ref "D12") (pin "2") (pinfunction "A_2") (pintype "passive"))
      (node (ref "R13") (pin "2") (pinfunction "2_2") (pintype "passive"))
    )
    (net (code "45") (name "Net-(D13-A)") (class "Default")
      (node (ref "D13") (pin "2") (pinfunction "A_2") (pintype "passive"))
      (node (ref "R14") (pin "2") (pinfunction "2_2") (pintype "passive"))
    )
    (net (code "46") (name "Net-(D14-A)") (class "Default")
      (node (ref "D14") (pin "2") (pinfunction "A_2") (pintype "passive"))
      (node (ref "R15") (pin "2") (pinfunction "2_2") (pintype "passive"))
    )
    (net (code "47") (name "Net-(D15-A)") (class "Default")
      (node (ref "D15") (pin "2") (pinfunction "A_2") (pintype "passive"))
      (node (ref "R16") (pin "2") (pinfunction "2_2") (pintype "passive"))
    )
    (net (code "48") (name "Net-(D16-A)") (class "Default")
      (node (ref "D16") (pin "2") (pinfunction "A_2") (pintype "passive"))
      (node (ref "R17") (pin "2") (pinfunction "2_2") (pintype "passive"))
    )
    (net (code "49") (name "Net-(D17-A)") (class "Default")
      (node (ref "D17") (pin "2") (pinfunction "A_2") (pintype "passive"))
      (node (ref "R18") (pin "2") (pinfunction "2_2") (pintype "passive"))
    )
    (net (code "50") (name "Net-(D18-A)") (class "Default")
      (node (ref "D18") (pin "2") (pinfunction "A_2") (pintype "passive"))
      (node (ref "R19") (pin "2") (pinfunction "2_2") (pintype "passive"))
    )
    (net (code "51") (name "Net-(D19-A)") (class "Default")
      (node (ref "D19") (pin "2") (pinfunction "A_2") (pintype "passive"))
      (node (ref "R20") (pin "2") (pinfunction "2_2") (pintype "passive"))
    )
    (net (code "52") (name "Net-(D20-A)") (class "Default")
      (node (ref "D20") (pin "2") (pinfunction "A_2") (pintype "passive"))
      (node (ref "R21") (pin "2") (pinfunction "2_2") (pintype "passive"))
    )
    (net (code "53") (name "Net-(D21-A)") (class "Default")
      (node (ref "D21") (pin "2") (pinfunction "A_2") (pintype "passive"))
      (node (ref "R22") (pin "2") (pinfunction "2_2") (pintype "passive"))
    )
    (net (code "54") (name "Net-(D22-A)") (class "Default")
      (node (ref "D22") (pin "2") (pinfunction "A_2") (pintype "passive"))
      (node (ref "R23") (pin "2") (pinfunction "2_2") (pintype "passive"))
    )
    (net (code "55") (name "Net-(D23-A)") (class "Default")
      (node (ref "D23") (pin "2") (pinfunction "A_2") (pintype "passive"))
      (node (ref "R24") (pin "2") (pinfunction "2_2") (pintype "passive"))
    )
    (net (code "56") (name "Net-(D24-A)") (class "Default")
      (node (ref "D24") (pin "2") (pinfunction "A_2") (pintype "passive"))
      (node (ref "R25") (pin "2") (pinfunction "2_2") (pintype "passive"))
    )
  )
)
